# Sheet5.net
KiCad netlist of a schematic drawn in Altium Designer
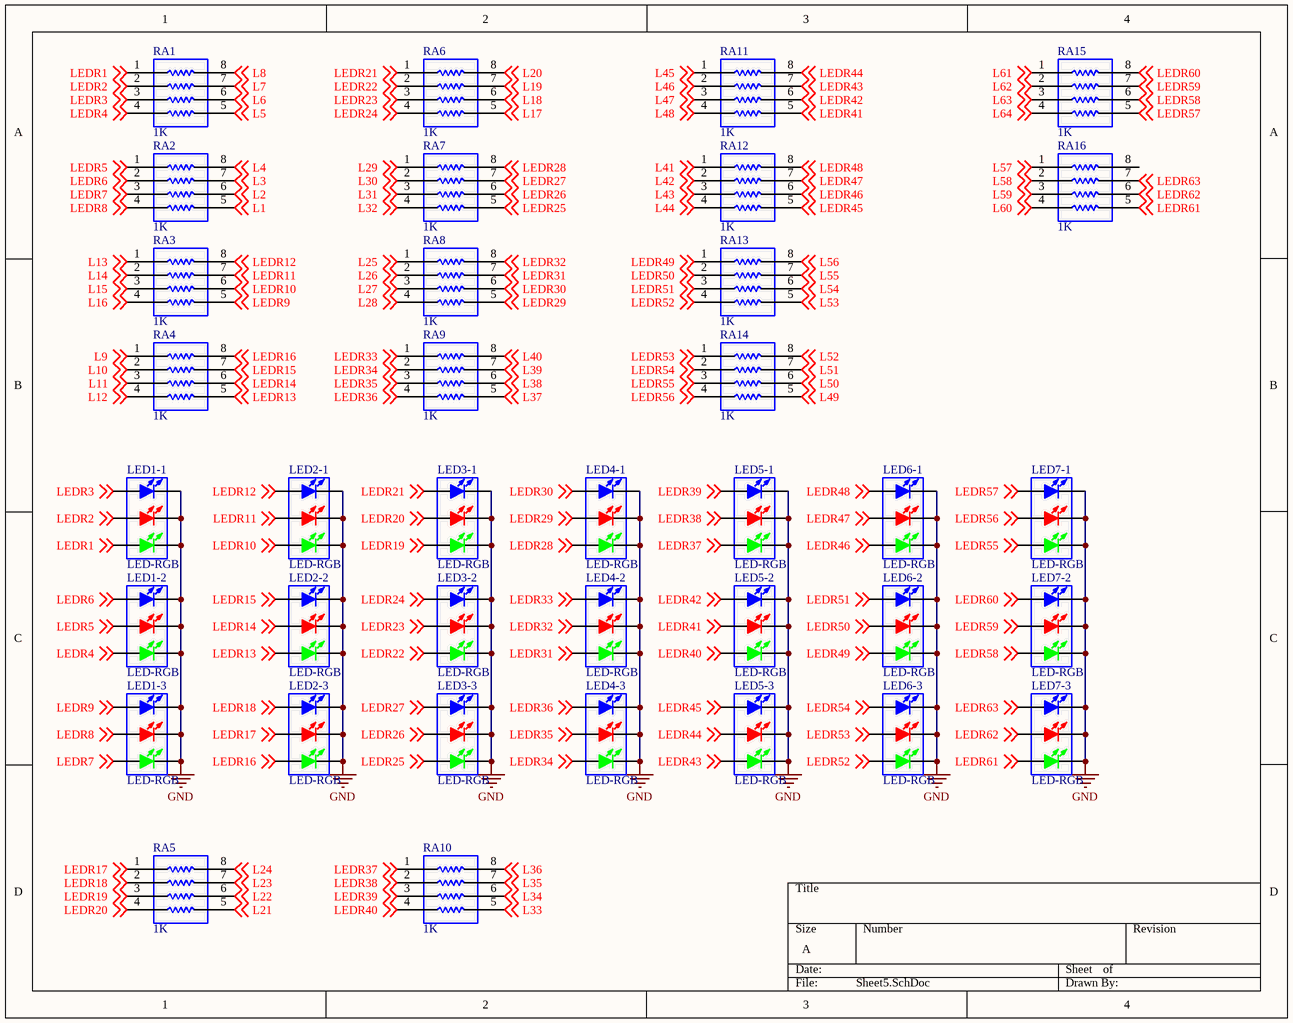
[diagram p0: Sheet5.SchDoc]

(export (version "E")
  (design (tool "Eeschema 10.0.6"))
  (components
    (comp (ref "LED1-1")
      (value "LED-RGB")
      (footprint "LED 5050")
      (description "Three primary color LED")
      (fields (field (name "版权归属") "源创客"))
      (libsource (lib "LED") (part "LED-RGB"))
    )
    (comp (ref "LED1-2")
      (value "LED-RGB")
      (footprint "LED 5050")
      (description "Three primary color LED")
      (fields (field (name "版权归属") "源创客"))
      (libsource (lib "LED") (part "LED-RGB"))
    )
    (comp (ref "LED1-3")
      (value "LED-RGB")
      (footprint "LED 5050")
      (description "Three primary color LED")
      (fields (field (name "版权归属") "源创客"))
      (libsource (lib "LED") (part "LED-RGB"))
    )
    (comp (ref "LED2-1")
      (value "LED-RGB")
      (footprint "LED 5050")
      (description "Three primary color LED")
      (fields (field (name "版权归属") "源创客"))
      (libsource (lib "LED") (part "LED-RGB"))
    )
    (comp (ref "LED2-2")
      (value "LED-RGB")
      (footprint "LED 5050")
      (description "Three primary color LED")
      (fields (field (name "版权归属") "源创客"))
      (libsource (lib "LED") (part "LED-RGB"))
    )
    (comp (ref "LED2-3")
      (value "LED-RGB")
      (footprint "LED 5050")
      (description "Three primary color LED")
      (fields (field (name "版权归属") "源创客"))
      (libsource (lib "LED") (part "LED-RGB"))
    )
    (comp (ref "LED3-1")
      (value "LED-RGB")
      (footprint "LED 5050")
      (description "Three primary color LED")
      (fields (field (name "版权归属") "源创客"))
      (libsource (lib "LED") (part "LED-RGB"))
    )
    (comp (ref "LED3-2")
      (value "LED-RGB")
      (footprint "LED 5050")
      (description "Three primary color LED")
      (fields (field (name "版权归属") "源创客"))
      (libsource (lib "LED") (part "LED-RGB"))
    )
    (comp (ref "LED3-3")
      (value "LED-RGB")
      (footprint "LED 5050")
      (description "Three primary color LED")
      (fields (field (name "版权归属") "源创客"))
      (libsource (lib "LED") (part "LED-RGB"))
    )
    (comp (ref "LED4-1")
      (value "LED-RGB")
      (footprint "LED 5050")
      (description "Three primary color LED")
      (fields (field (name "版权归属") "源创客"))
      (libsource (lib "LED") (part "LED-RGB"))
    )
    (comp (ref "LED4-2")
      (value "LED-RGB")
      (footprint "LED 5050")
      (description "Three primary color LED")
      (fields (field (name "版权归属") "源创客"))
      (libsource (lib "LED") (part "LED-RGB"))
    )
    (comp (ref "LED4-3")
      (value "LED-RGB")
      (footprint "LED 5050")
      (description "Three primary color LED")
      (fields (field (name "版权归属") "源创客"))
      (libsource (lib "LED") (part "LED-RGB"))
    )
    (comp (ref "LED5-1")
      (value "LED-RGB")
      (footprint "LED 5050")
      (description "Three primary color LED")
      (fields (field (name "版权归属") "源创客"))
      (libsource (lib "LED") (part "LED-RGB"))
    )
    (comp (ref "LED5-2")
      (value "LED-RGB")
      (footprint "LED 5050")
      (description "Three primary color LED")
      (fields (field (name "版权归属") "源创客"))
      (libsource (lib "LED") (part "LED-RGB"))
    )
    (comp (ref "LED5-3")
      (value "LED-RGB")
      (footprint "LED 5050")
      (description "Three primary color LED")
      (fields (field (name "版权归属") "源创客"))
      (libsource (lib "LED") (part "LED-RGB"))
    )
    (comp (ref "LED6-1")
      (value "LED-RGB")
      (footprint "LED 5050")
      (description "Three primary color LED")
      (fields (field (name "版权归属") "源创客"))
      (libsource (lib "LED") (part "LED-RGB"))
    )
    (comp (ref "LED6-2")
      (value "LED-RGB")
      (footprint "LED 5050")
      (description "Three primary color LED")
      (fields (field (name "版权归属") "源创客"))
      (libsource (lib "LED") (part "LED-RGB"))
    )
    (comp (ref "LED6-3")
      (value "LED-RGB")
      (footprint "LED 5050")
      (description "Three primary color LED")
      (fields (field (name "版权归属") "源创客"))
      (libsource (lib "LED") (part "LED-RGB"))
    )
    (comp (ref "LED7-1")
      (value "LED-RGB")
      (footprint "LED 5050")
      (description "Three primary color LED")
      (fields (field (name "版权归属") "源创客"))
      (libsource (lib "LED") (part "LED-RGB"))
    )
    (comp (ref "LED7-2")
      (value "LED-RGB")
      (footprint "LED 5050")
      (description "Three primary color LED")
      (fields (field (name "版权归属") "源创客"))
      (libsource (lib "LED") (part "LED-RGB"))
    )
    (comp (ref "LED7-3")
      (value "LED-RGB")
      (footprint "LED 5050")
      (description "Three primary color LED")
      (fields (field (name "版权归属") "源创客"))
      (libsource (lib "LED") (part "LED-RGB"))
    )
    (comp (ref "RA1")
      (value "1K")
      (footprint "RA1206 (4x0603)")
      (description "4 way Chip Resistor Array")
      (libsource (lib "Passive (Resistor-Capacitor-Inductor-Veristor-Ferrite)") (part "R-ARR"))
    )
    (comp (ref "RA2")
      (value "1K")
      (footprint "RA1206 (4x0603)")
      (description "4 way Chip Resistor Array")
      (libsource (lib "Passive (Resistor-Capacitor-Inductor-Veristor-Ferrite)") (part "R-ARR"))
    )
    (comp (ref "RA3")
      (value "1K")
      (footprint "RA1206 (4x0603)")
      (description "4 way Chip Resistor Array")
      (libsource (lib "Passive (Resistor-Capacitor-Inductor-Veristor-Ferrite)") (part "R-ARR"))
    )
    (comp (ref "RA4")
      (value "1K")
      (footprint "RA1206 (4x0603)")
      (description "4 way Chip Resistor Array")
      (libsource (lib "Passive (Resistor-Capacitor-Inductor-Veristor-Ferrite)") (part "R-ARR"))
    )
    (comp (ref "RA5")
      (value "1K")
      (footprint "RA1206 (4x0603)")
      (description "4 way Chip Resistor Array")
      (libsource (lib "Passive (Resistor-Capacitor-Inductor-Veristor-Ferrite)") (part "R-ARR"))
    )
    (comp (ref "RA6")
      (value "1K")
      (footprint "RA1206 (4x0603)")
      (description "4 way Chip Resistor Array")
      (libsource (lib "Passive (Resistor-Capacitor-Inductor-Veristor-Ferrite)") (part "R-ARR"))
    )
    (comp (ref "RA7")
      (value "1K")
      (footprint "RA1206 (4x0603)")
      (description "4 way Chip Resistor Array")
      (libsource (lib "Passive (Resistor-Capacitor-Inductor-Veristor-Ferrite)") (part "R-ARR"))
    )
    (comp (ref "RA8")
      (value "1K")
      (footprint "RA1206 (4x0603)")
      (description "4 way Chip Resistor Array")
      (libsource (lib "Passive (Resistor-Capacitor-Inductor-Veristor-Ferrite)") (part "R-ARR"))
    )
    (comp (ref "RA9")
      (value "1K")
      (footprint "RA1206 (4x0603)")
      (description "4 way Chip Resistor Array")
      (libsource (lib "Passive (Resistor-Capacitor-Inductor-Veristor-Ferrite)") (part "R-ARR"))
    )
    (comp (ref "RA10")
      (value "1K")
      (footprint "RA1206 (4x0603)")
      (description "4 way Chip Resistor Array")
      (libsource (lib "Passive (Resistor-Capacitor-Inductor-Veristor-Ferrite)") (part "R-ARR"))
    )
    (comp (ref "RA11")
      (value "1K")
      (footprint "RA1206 (4x0603)")
      (description "4 way Chip Resistor Array")
      (libsource (lib "Passive (Resistor-Capacitor-Inductor-Veristor-Ferrite)") (part "R-ARR"))
    )
    (comp (ref "RA12")
      (value "1K")
      (footprint "RA1206 (4x0603)")
      (description "4 way Chip Resistor Array")
      (libsource (lib "Passive (Resistor-Capacitor-Inductor-Veristor-Ferrite)") (part "R-ARR"))
    )
    (comp (ref "RA13")
      (value "1K")
      (footprint "RA1206 (4x0603)")
      (description "4 way Chip Resistor Array")
      (libsource (lib "Passive (Resistor-Capacitor-Inductor-Veristor-Ferrite)") (part "R-ARR"))
    )
    (comp (ref "RA14")
      (value "1K")
      (footprint "RA1206 (4x0603)")
      (description "4 way Chip Resistor Array")
      (libsource (lib "Passive (Resistor-Capacitor-Inductor-Veristor-Ferrite)") (part "R-ARR"))
    )
    (comp (ref "RA15")
      (value "1K")
      (footprint "RA1206 (4x0603)")
      (description "4 way Chip Resistor Array")
      (libsource (lib "Passive (Resistor-Capacitor-Inductor-Veristor-Ferrite)") (part "R-ARR"))
    )
    (comp (ref "RA16")
      (value "1K")
      (footprint "RA1206 (4x0603)")
      (description "4 way Chip Resistor Array")
      (libsource (lib "Passive (Resistor-Capacitor-Inductor-Veristor-Ferrite)") (part "R-ARR"))
    )
  )
  (nets
    (net (code "1") (name "GND") (class "Default")
      (node (ref "LED1-1") (pin "2") (pinfunction "BULE_K_2") (pintype "passive"))
      (node (ref "LED1-1") (pin "4") (pinfunction "RED_K_4") (pintype "passive"))
      (node (ref "LED1-1") (pin "6") (pinfunction "GREEN_K_6") (pintype "passive"))
      (node (ref "LED1-2") (pin "2") (pinfunction "BULE_K_2") (pintype "passive"))
      (node (ref "LED1-2") (pin "4") (pinfunction "RED_K_4") (pintype "passive"))
      (node (ref "LED1-2") (pin "6") (pinfunction "GREEN_K_6") (pintype "passive"))
      (node (ref "LED1-3") (pin "2") (pinfunction "BULE_K_2") (pintype "passive"))
      (node (ref "LED1-3") (pin "4") (pinfunction "RED_K_4") (pintype "passive"))
      (node (ref "LED1-3") (pin "6") (pinfunction "GREEN_K_6") (pintype "passive"))
      (node (ref "LED2-1") (pin "2") (pinfunction "BULE_K_2") (pintype "passive"))
      (node (ref "LED2-1") (pin "4") (pinfunction "RED_K_4") (pintype "passive"))
      (node (ref "LED2-1") (pin "6") (pinfunction "GREEN_K_6") (pintype "passive"))
      (node (ref "LED2-2") (pin "2") (pinfunction "BULE_K_2") (pintype "passive"))
      (node (ref "LED2-2") (pin "4") (pinfunction "RED_K_4") (pintype "passive"))
      (node (ref "LED2-2") (pin "6") (pinfunction "GREEN_K_6") (pintype "passive"))
      (node (ref "LED2-3") (pin "2") (pinfunction "BULE_K_2") (pintype "passive"))
      (node (ref "LED2-3") (pin "4") (pinfunction "RED_K_4") (pintype "passive"))
      (node (ref "LED2-3") (pin "6") (pinfunction "GREEN_K_6") (pintype "passive"))
      (node (ref "LED3-1") (pin "2") (pinfunction "BULE_K_2") (pintype "passive"))
      (node (ref "LED3-1") (pin "4") (pinfunction "RED_K_4") (pintype "passive"))
      (node (ref "LED3-1") (pin "6") (pinfunction "GREEN_K_6") (pintype "passive"))
      (node (ref "LED3-2") (pin "2") (pinfunction "BULE_K_2") (pintype "passive"))
      (node (ref "LED3-2") (pin "4") (pinfunction "RED_K_4") (pintype "passive"))
      (node (ref "LED3-2") (pin "6") (pinfunction "GREEN_K_6") (pintype "passive"))
      (node (ref "LED3-3") (pin "2") (pinfunction "BULE_K_2") (pintype "passive"))
      (node (ref "LED3-3") (pin "4") (pinfunction "RED_K_4") (pintype "passive"))
      (node (ref "LED3-3") (pin "6") (pinfunction "GREEN_K_6") (pintype "passive"))
      (node (ref "LED4-1") (pin "2") (pinfunction "BULE_K_2") (pintype "passive"))
      (node (ref "LED4-1") (pin "4") (pinfunction "RED_K_4") (pintype "passive"))
      (node (ref "LED4-1") (pin "6") (pinfunction "GREEN_K_6") (pintype "passive"))
      (node (ref "LED4-2") (pin "2") (pinfunction "BULE_K_2") (pintype "passive"))
      (node (ref "LED4-2") (pin "4") (pinfunction "RED_K_4") (pintype "passive"))
      (node (ref "LED4-2") (pin "6") (pinfunction "GREEN_K_6") (pintype "passive"))
      (node (ref "LED4-3") (pin "2") (pinfunction "BULE_K_2") (pintype "passive"))
      (node (ref "LED4-3") (pin "4") (pinfunction "RED_K_4") (pintype "passive"))
      (node (ref "LED4-3") (pin "6") (pinfunction "GREEN_K_6") (pintype "passive"))
      (node (ref "LED5-1") (pin "2") (pinfunction "BULE_K_2") (pintype "passive"))
      (node (ref "LED5-1") (pin "4") (pinfunction "RED_K_4") (pintype "passive"))
      (node (ref "LED5-1") (pin "6") (pinfunction "GREEN_K_6") (pintype "passive"))
      (node (ref "LED5-2") (pin "2") (pinfunction "BULE_K_2") (pintype "passive"))
      (node (ref "LED5-2") (pin "4") (pinfunction "RED_K_4") (pintype "passive"))
      (node (ref "LED5-2") (pin "6") (pinfunction "GREEN_K_6") (pintype "passive"))
      (node (ref "LED5-3") (pin "2") (pinfunction "BULE_K_2") (pintype "passive"))
      (node (ref "LED5-3") (pin "4") (pinfunction "RED_K_4") (pintype "passive"))
      (node (ref "LED5-3") (pin "6") (pinfunction "GREEN_K_6") (pintype "passive"))
      (node (ref "LED6-1") (pin "2") (pinfunction "BULE_K_2") (pintype "passive"))
      (node (ref "LED6-1") (pin "4") (pinfunction "RED_K_4") (pintype "passive"))
      (node (ref "LED6-1") (pin "6") (pinfunction "GREEN_K_6") (pintype "passive"))
      (node (ref "LED6-2") (pin "2") (pinfunction "BULE_K_2") (pintype "passive"))
      (node (ref "LED6-2") (pin "4") (pinfunction "RED_K_4") (pintype "passive"))
      (node (ref "LED6-2") (pin "6") (pinfunction "GREEN_K_6") (pintype "passive"))
      (node (ref "LED6-3") (pin "2") (pinfunction "BULE_K_2") (pintype "passive"))
      (node (ref "LED6-3") (pin "4") (pinfunction "RED_K_4") (pintype "passive"))
      (node (ref "LED6-3") (pin "6") (pinfunction "GREEN_K_6") (pintype "passive"))
      (node (ref "LED7-1") (pin "2") (pinfunction "BULE_K_2") (pintype "passive"))
      (node (ref "LED7-1") (pin "4") (pinfunction "RED_K_4") (pintype "passive"))
      (node (ref "LED7-1") (pin "6") (pinfunction "GREEN_K_6") (pintype "passive"))
      (node (ref "LED7-2") (pin "2") (pinfunction "BULE_K_2") (pintype "passive"))
      (node (ref "LED7-2") (pin "4") (pinfunction "RED_K_4") (pintype "passive"))
      (node (ref "LED7-2") (pin "6") (pinfunction "GREEN_K_6") (pintype "passive"))
      (node (ref "LED7-3") (pin "2") (pinfunction "BULE_K_2") (pintype "passive"))
      (node (ref "LED7-3") (pin "4") (pinfunction "RED_K_4") (pintype "passive"))
      (node (ref "LED7-3") (pin "6") (pinfunction "GREEN_K_6") (pintype "passive"))
    )
    (net (code "2") (name "L1") (class "Default")
      (node (ref "RA2") (pin "5") (pinfunction "5_5") (pintype "passive"))
    )
    (net (code "3") (name "L2") (class "Default")
      (node (ref "RA2") (pin "6") (pinfunction "6_6") (pintype "passive"))
    )
    (net (code "4") (name "L3") (class "Default")
      (node (ref "RA2") (pin "7") (pinfunction "7_7") (pintype "passive"))
    )
    (net (code "5") (name "L4") (class "Default")
      (node (ref "RA2") (pin "8") (pinfunction "8_8") (pintype "passive"))
    )
    (net (code "6") (name "L5") (class "Default")
      (node (ref "RA1") (pin "5") (pinfunction "5_5") (pintype "passive"))
    )
    (net (code "7") (name "L6") (class "Default")
      (node (ref "RA1") (pin "6") (pinfunction "6_6") (pintype "passive"))
    )
    (net (code "8") (name "L7") (class "Default")
      (node (ref "RA1") (pin "7") (pinfunction "7_7") (pintype "passive"))
    )
    (net (code "9") (name "L8") (class "Default")
      (node (ref "RA1") (pin "8") (pinfunction "8_8") (pintype "passive"))
    )
    (net (code "10") (name "L9") (class "Default")
      (node (ref "RA4") (pin "1") (pinfunction "1_1") (pintype "passive"))
    )
    (net (code "11") (name "L10") (class "Default")
      (node (ref "RA4") (pin "2") (pinfunction "2_2") (pintype "passive"))
    )
    (net (code "12") (name "L11") (class "Default")
      (node (ref "RA4") (pin "3") (pinfunction "3_3") (pintype "passive"))
    )
    (net (code "13") (name "L12") (class "Default")
      (node (ref "RA4") (pin "4") (pinfunction "4_4") (pintype "passive"))
    )
    (net (code "14") (name "L13") (class "Default")
      (node (ref "RA3") (pin "1") (pinfunction "1_1") (pintype "passive"))
    )
    (net (code "15") (name "L14") (class "Default")
      (node (ref "RA3") (pin "2") (pinfunction "2_2") (pintype "passive"))
    )
    (net (code "16") (name "L15") (class "Default")
      (node (ref "RA3") (pin "3") (pinfunction "3_3") (pintype "passive"))
    )
    (net (code "17") (name "L16") (class "Default")
      (node (ref "RA3") (pin "4") (pinfunction "4_4") (pintype "passive"))
    )
    (net (code "18") (name "L17") (class "Default")
      (node (ref "RA6") (pin "5") (pinfunction "5_5") (pintype "passive"))
    )
    (net (code "19") (name "L18") (class "Default")
      (node (ref "RA6") (pin "6") (pinfunction "6_6") (pintype "passive"))
    )
    (net (code "20") (name "L19") (class "Default")
      (node (ref "RA6") (pin "7") (pinfunction "7_7") (pintype "passive"))
    )
    (net (code "21") (name "L20") (class "Default")
      (node (ref "RA6") (pin "8") (pinfunction "8_8") (pintype "passive"))
    )
    (net (code "22") (name "L21") (class "Default")
      (node (ref "RA5") (pin "5") (pinfunction "5_5") (pintype "passive"))
    )
    (net (code "23") (name "L22") (class "Default")
      (node (ref "RA5") (pin "6") (pinfunction "6_6") (pintype "passive"))
    )
    (net (code "24") (name "L23") (class "Default")
      (node (ref "RA5") (pin "7") (pinfunction "7_7") (pintype "passive"))
    )
    (net (code "25") (name "L24") (class "Default")
      (node (ref "RA5") (pin "8") (pinfunction "8_8") (pintype "passive"))
    )
    (net (code "26") (name "L25") (class "Default")
      (node (ref "RA8") (pin "1") (pinfunction "1_1") (pintype "passive"))
    )
    (net (code "27") (name "L26") (class "Default")
      (node (ref "RA8") (pin "2") (pinfunction "2_2") (pintype "passive"))
    )
    (net (code "28") (name "L27") (class "Default")
      (node (ref "RA8") (pin "3") (pinfunction "3_3") (pintype "passive"))
    )
    (net (code "29") (name "L28") (class "Default")
      (node (ref "RA8") (pin "4") (pinfunction "4_4") (pintype "passive"))
    )
    (net (code "30") (name "L29") (class "Default")
      (node (ref "RA7") (pin "1") (pinfunction "1_1") (pintype "passive"))
    )
    (net (code "31") (name "L30") (class "Default")
      (node (ref "RA7") (pin "2") (pinfunction "2_2") (pintype "passive"))
    )
    (net (code "32") (name "L31") (class "Default")
      (node (ref "RA7") (pin "3") (pinfunction "3_3") (pintype "passive"))
    )
    (net (code "33") (name "L32") (class "Default")
      (node (ref "RA7") (pin "4") (pinfunction "4_4") (pintype "passive"))
    )
    (net (code "34") (name "L33") (class "Default")
      (node (ref "RA10") (pin "5") (pinfunction "5_5") (pintype "passive"))
    )
    (net (code "35") (name "L34") (class "Default")
      (node (ref "RA10") (pin "6") (pinfunction "6_6") (pintype "passive"))
    )
    (net (code "36") (name "L35") (class "Default")
      (node (ref "RA10") (pin "7") (pinfunction "7_7") (pintype "passive"))
    )
    (net (code "37") (name "L36") (class "Default")
      (node (ref "RA10") (pin "8") (pinfunction "8_8") (pintype "passive"))
    )
    (net (code "38") (name "L37") (class "Default")
      (node (ref "RA9") (pin "5") (pinfunction "5_5") (pintype "passive"))
    )
    (net (code "39") (name "L38") (class "Default")
      (node (ref "RA9") (pin "6") (pinfunction "6_6") (pintype "passive"))
    )
    (net (code "40") (name "L39") (class "Default")
      (node (ref "RA9") (pin "7") (pinfunction "7_7") (pintype "passive"))
    )
    (net (code "41") (name "L40") (class "Default")
      (node (ref "RA9") (pin "8") (pinfunction "8_8") (pintype "passive"))
    )
    (net (code "42") (name "L41") (class "Default")
      (node (ref "RA12") (pin "1") (pinfunction "1_1") (pintype "passive"))
    )
    (net (code "43") (name "L42") (class "Default")
      (node (ref "RA12") (pin "2") (pinfunction "2_2") (pintype "passive"))
    )
    (net (code "44") (name "L43") (class "Default")
      (node (ref "RA12") (pin "3") (pinfunction "3_3") (pintype "passive"))
    )
    (net (code "45") (name "L44") (class "Default")
      (node (ref "RA12") (pin "4") (pinfunction "4_4") (pintype "passive"))
    )
    (net (code "46") (name "L45") (class "Default")
      (node (ref "RA11") (pin "1") (pinfunction "1_1") (pintype "passive"))
    )
    (net (code "47") (name "L46") (class "Default")
      (node (ref "RA11") (pin "2") (pinfunction "2_2") (pintype "passive"))
    )
    (net (code "48") (name "L47") (class "Default")
      (node (ref "RA11") (pin "3") (pinfunction "3_3") (pintype "passive"))
    )
    (net (code "49") (name "L48") (class "Default")
      (node (ref "RA11") (pin "4") (pinfunction "4_4") (pintype "passive"))
    )
    (net (code "50") (name "L49") (class "Default")
      (node (ref "RA14") (pin "5") (pinfunction "5_5") (pintype "passive"))
    )
    (net (code "51") (name "L50") (class "Default")
      (node (ref "RA14") (pin "6") (pinfunction "6_6") (pintype "passive"))
    )
    (net (code "52") (name "L51") (class "Default")
      (node (ref "RA14") (pin "7") (pinfunction "7_7") (pintype "passive"))
    )
    (net (code "53") (name "L52") (class "Default")
      (node (ref "RA14") (pin "8") (pinfunction "8_8") (pintype "passive"))
    )
    (net (code "54") (name "L53") (class "Default")
      (node (ref "RA13") (pin "5") (pinfunction "5_5") (pintype "passive"))
    )
    (net (code "55") (name "L54") (class "Default")
      (node (ref "RA13") (pin "6") (pinfunction "6_6") (pintype "passive"))
    )
    (net (code "56") (name "L55") (class "Default")
      (node (ref "RA13") (pin "7") (pinfunction "7_7") (pintype "passive"))
    )
    (net (code "57") (name "L56") (class "Default")
      (node (ref "RA13") (pin "8") (pinfunction "8_8") (pintype "passive"))
    )
    (net (code "58") (name "L57") (class "Default")
      (node (ref "RA16") (pin "1") (pinfunction "1_1") (pintype "passive"))
    )
    (net (code "59") (name "L58") (class "Default")
      (node (ref "RA16") (pin "2") (pinfunction "2_2") (pintype "passive"))
    )
    (net (code "60") (name "L59") (class "Default")
      (node (ref "RA16") (pin "3") (pinfunction "3_3") (pintype "passive"))
    )
    (net (code "61") (name "L60") (class "Default")
      (node (ref "RA16") (pin "4") (pinfunction "4_4") (pintype "passive"))
    )
    (net (code "62") (name "L61") (class "Default")
      (node (ref "RA15") (pin "1") (pinfunction "1_1") (pintype "passive"))
    )
    (net (code "63") (name "L62") (class "Default")
      (node (ref "RA15") (pin "2") (pinfunction "2_2") (pintype "passive"))
    )
    (net (code "64") (name "L63") (class "Default")
      (node (ref "RA15") (pin "3") (pinfunction "3_3") (pintype "passive"))
    )
    (net (code "65") (name "L64") (class "Default")
      (node (ref "RA15") (pin "4") (pinfunction "4_4") (pintype "passive"))
    )
    (net (code "66") (name "LEDR1") (class "Default")
      (node (ref "LED1-1") (pin "5") (pinfunction "GREEN_A_5") (pintype "passive"))
      (node (ref "RA1") (pin "1") (pinfunction "1_1") (pintype "passive"))
    )
    (net (code "67") (name "LEDR2") (class "Default")
      (node (ref "LED1-1") (pin "3") (pinfunction "RED_A_3") (pintype "passive"))
      (node (ref "RA1") (pin "2") (pinfunction "2_2") (pintype "passive"))
    )
    (net (code "68") (name "LEDR3") (class "Default")
      (node (ref "LED1-1") (pin "1") (pinfunction "BULE_A_1") (pintype "passive"))
      (node (ref "RA1") (pin "3") (pinfunction "3_3") (pintype "passive"))
    )
    (net (code "69") (name "LEDR4") (class "Default")
      (node (ref "LED1-2") (pin "5") (pinfunction "GREEN_A_5") (pintype "passive"))
      (node (ref "RA1") (pin "4") (pinfunction "4_4") (pintype "passive"))
    )
    (net (code "70") (name "LEDR5") (class "Default")
      (node (ref "LED1-2") (pin "3") (pinfunction "RED_A_3") (pintype "passive"))
      (node (ref "RA2") (pin "1") (pinfunction "1_1") (pintype "passive"))
    )
    (net (code "71") (name "LEDR6") (class "Default")
      (node (ref "LED1-2") (pin "1") (pinfunction "BULE_A_1") (pintype "passive"))
      (node (ref "RA2") (pin "2") (pinfunction "2_2") (pintype "passive"))
    )
    (net (code "72") (name "LEDR7") (class "Default")
      (node (ref "LED1-3") (pin "5") (pinfunction "GREEN_A_5") (pintype "passive"))
      (node (ref "RA2") (pin "3") (pinfunction "3_3") (pintype "passive"))
    )
    (net (code "73") (name "LEDR8") (class "Default")
      (node (ref "LED1-3") (pin "3") (pinfunction "RED_A_3") (pintype "passive"))
      (node (ref "RA2") (pin "4") (pinfunction "4_4") (pintype "passive"))
    )
    (net (code "74") (name "LEDR9") (class "Default")
      (node (ref "LED1-3") (pin "1") (pinfunction "BULE_A_1") (pintype "passive"))
      (node (ref "RA3") (pin "5") (pinfunction "5_5") (pintype "passive"))
    )
    (net (code "75") (name "LEDR10") (class "Default")
      (node (ref "LED2-1") (pin "5") (pinfunction "GREEN_A_5") (pintype "passive"))
      (node (ref "RA3") (pin "6") (pinfunction "6_6") (pintype "passive"))
    )
    (net (code "76") (name "LEDR11") (class "Default")
      (node (ref "LED2-1") (pin "3") (pinfunction "RED_A_3") (pintype "passive"))
      (node (ref "RA3") (pin "7") (pinfunction "7_7") (pintype "passive"))
    )
    (net (code "77") (name "LEDR12") (class "Default")
      (node (ref "LED2-1") (pin "1") (pinfunction "BULE_A_1") (pintype "passive"))
      (node (ref "RA3") (pin "8") (pinfunction "8_8") (pintype "passive"))
    )
    (net (code "78") (name "LEDR13") (class "Default")
      (node (ref "LED2-2") (pin "5") (pinfunction "GREEN_A_5") (pintype "passive"))
      (node (ref "RA4") (pin "5") (pinfunction "5_5") (pintype "passive"))
    )
    (net (code "79") (name "LEDR14") (class "Default")
      (node (ref "LED2-2") (pin "3") (pinfunction "RED_A_3") (pintype "passive"))
      (node (ref "RA4") (pin "6") (pinfunction "6_6") (pintype "passive"))
    )
    (net (code "80") (name "LEDR15") (class "Default")
      (node (ref "LED2-2") (pin "1") (pinfunction "BULE_A_1") (pintype "passive"))
      (node (ref "RA4") (pin "7") (pinfunction "7_7") (pintype "passive"))
    )
    (net (code "81") (name "LEDR16") (class "Default")
      (node (ref "LED2-3") (pin "5") (pinfunction "GREEN_A_5") (pintype "passive"))
      (node (ref "RA4") (pin "8") (pinfunction "8_8") (pintype "passive"))
    )
    (net (code "82") (name "LEDR17") (class "Default")
      (node (ref "LED2-3") (pin "3") (pinfunction "RED_A_3") (pintype "passive"))
      (node (ref "RA5") (pin "1") (pinfunction "1_1") (pintype "passive"))
    )
    (net (code "83") (name "LEDR18") (class "Default")
      (node (ref "LED2-3") (pin "1") (pinfunction "BULE_A_1") (pintype "passive"))
      (node (ref "RA5") (pin "2") (pinfunction "2_2") (pintype "passive"))
    )
    (net (code "84") (name "LEDR19") (class "Default")
      (node (ref "LED3-1") (pin "5") (pinfunction "GREEN_A_5") (pintype "passive"))
      (node (ref "RA5") (pin "3") (pinfunction "3_3") (pintype "passive"))
    )
    (net (code "85") (name "LEDR20") (class "Default")
      (node (ref "LED3-1") (pin "3") (pinfunction "RED_A_3") (pintype "passive"))
      (node (ref "RA5") (pin "4") (pinfunction "4_4") (pintype "passive"))
    )
    (net (code "86") (name "LEDR21") (class "Default")
      (node (ref "LED3-1") (pin "1") (pinfunction "BULE_A_1") (pintype "passive"))
      (node (ref "RA6") (pin "1") (pinfunction "1_1") (pintype "passive"))
    )
    (net (code "87") (name "LEDR22") (class "Default")
      (node (ref "LED3-2") (pin "5") (pinfunction "GREEN_A_5") (pintype "passive"))
      (node (ref "RA6") (pin "2") (pinfunction "2_2") (pintype "passive"))
    )
    (net (code "88") (name "LEDR23") (class "Default")
      (node (ref "LED3-2") (pin "3") (pinfunction "RED_A_3") (pintype "passive"))
      (node (ref "RA6") (pin "3") (pinfunction "3_3") (pintype "passive"))
    )
    (net (code "89") (name "LEDR24") (class "Default")
      (node (ref "LED3-2") (pin "1") (pinfunction "BULE_A_1") (pintype "passive"))
      (node (ref "RA6") (pin "4") (pinfunction "4_4") (pintype "passive"))
    )
    (net (code "90") (name "LEDR25") (class "Default")
      (node (ref "LED3-3") (pin "5") (pinfunction "GREEN_A_5") (pintype "passive"))
      (node (ref "RA7") (pin "5") (pinfunction "5_5") (pintype "passive"))
    )
    (net (code "91") (name "LEDR26") (class "Default")
      (node (ref "LED3-3") (pin "3") (pinfunction "RED_A_3") (pintype "passive"))
      (node (ref "RA7") (pin "6") (pinfunction "6_6") (pintype "passive"))
    )
    (net (code "92") (name "LEDR27") (class "Default")
      (node (ref "LED3-3") (pin "1") (pinfunction "BULE_A_1") (pintype "passive"))
      (node (ref "RA7") (pin "7") (pinfunction "7_7") (pintype "passive"))
    )
    (net (code "93") (name "LEDR28") (class "Default")
      (node (ref "LED4-1") (pin "5") (pinfunction "GREEN_A_5") (pintype "passive"))
      (node (ref "RA7") (pin "8") (pinfunction "8_8") (pintype "passive"))
    )
    (net (code "94") (name "LEDR29") (class "Default")
      (node (ref "LED4-1") (pin "3") (pinfunction "RED_A_3") (pintype "passive"))
      (node (ref "RA8") (pin "5") (pinfunction "5_5") (pintype "passive"))
    )
    (net (code "95") (name "LEDR30") (class "Default")
      (node (ref "LED4-1") (pin "1") (pinfunction "BULE_A_1") (pintype "passive"))
      (node (ref "RA8") (pin "6") (pinfunction "6_6") (pintype "passive"))
    )
    (net (code "96") (name "LEDR31") (class "Default")
      (node (ref "LED4-2") (pin "5") (pinfunction "GREEN_A_5") (pintype "passive"))
      (node (ref "RA8") (pin "7") (pinfunction "7_7") (pintype "passive"))
    )
    (net (code "97") (name "LEDR32") (class "Default")
      (node (ref "LED4-2") (pin "3") (pinfunction "RED_A_3") (pintype "passive"))
      (node (ref "RA8") (pin "8") (pinfunction "8_8") (pintype "passive"))
    )
    (net (code "98") (name "LEDR33") (class "Default")
      (node (ref "LED4-2") (pin "1") (pinfunction "BULE_A_1") (pintype "passive"))
      (node (ref "RA9") (pin "1") (pinfunction "1_1") (pintype "passive"))
    )
    (net (code "99") (name "LEDR34") (class "Default")
      (node (ref "LED4-3") (pin "5") (pinfunction "GREEN_A_5") (pintype "passive"))
      (node (ref "RA9") (pin "2") (pinfunction "2_2") (pintype "passive"))
    )
    (net (code "100") (name "LEDR35") (class "Default")
      (node (ref "LED4-3") (pin "3") (pinfunction "RED_A_3") (pintype "passive"))
      (node (ref "RA9") (pin "3") (pinfunction "3_3") (pintype "passive"))
    )
    (net (code "101") (name "LEDR36") (class "Default")
      (node (ref "LED4-3") (pin "1") (pinfunction "BULE_A_1") (pintype "passive"))
      (node (ref "RA9") (pin "4") (pinfunction "4_4") (pintype "passive"))
    )
    (net (code "102") (name "LEDR37") (class "Default")
      (node (ref "LED5-1") (pin "5") (pinfunction "GREEN_A_5") (pintype "passive"))
      (node (ref "RA10") (pin "1") (pinfunction "1_1") (pintype "passive"))
    )
    (net (code "103") (name "LEDR38") (class "Default")
      (node (ref "LED5-1") (pin "3") (pinfunction "RED_A_3") (pintype "passive"))
      (node (ref "RA10") (pin "2") (pinfunction "2_2") (pintype "passive"))
    )
    (net (code "104") (name "LEDR39") (class "Default")
      (node (ref "LED5-1") (pin "1") (pinfunction "BULE_A_1") (pintype "passive"))
      (node (ref "RA10") (pin "3") (pinfunction "3_3") (pintype "passive"))
    )
    (net (code "105") (name "LEDR40") (class "Default")
      (node (ref "LED5-2") (pin "5") (pinfunction "GREEN_A_5") (pintype "passive"))
      (node (ref "RA10") (pin "4") (pinfunction "4_4") (pintype "passive"))
    )
    (net (code "106") (name "LEDR41") (class "Default")
      (node (ref "LED5-2") (pin "3") (pinfunction "RED_A_3") (pintype "passive"))
      (node (ref "RA11") (pin "5") (pinfunction "5_5") (pintype "passive"))
    )
    (net (code "107") (name "LEDR42") (class "Default")
      (node (ref "LED5-2") (pin "1") (pinfunction "BULE_A_1") (pintype "passive"))
      (node (ref "RA11") (pin "6") (pinfunction "6_6") (pintype "passive"))
    )
    (net (code "108") (name "LEDR43") (class "Default")
      (node (ref "LED5-3") (pin "5") (pinfunction "GREEN_A_5") (pintype "passive"))
      (node (ref "RA11") (pin "7") (pinfunction "7_7") (pintype "passive"))
    )
    (net (code "109") (name "LEDR44") (class "Default")
      (node (ref "LED5-3") (pin "3") (pinfunction "RED_A_3") (pintype "passive"))
      (node (ref "RA11") (pin "8") (pinfunction "8_8") (pintype "passive"))
    )
    (net (code "110") (name "LEDR45") (class "Default")
      (node (ref "LED5-3") (pin "1") (pinfunction "BULE_A_1") (pintype "passive"))
      (node (ref "RA12") (pin "5") (pinfunction "5_5") (pintype "passive"))
    )
    (net (code "111") (name "LEDR46") (class "Default")
      (node (ref "LED6-1") (pin "5") (pinfunction "GREEN_A_5") (pintype "passive"))
      (node (ref "RA12") (pin "6") (pinfunction "6_6") (pintype "passive"))
    )
    (net (code "112") (name "LEDR47") (class "Default")
      (node (ref "LED6-1") (pin "3") (pinfunction "RED_A_3") (pintype "passive"))
      (node (ref "RA12") (pin "7") (pinfunction "7_7") (pintype "passive"))
    )
    (net (code "113") (name "LEDR48") (class "Default")
      (node (ref "LED6-1") (pin "1") (pinfunction "BULE_A_1") (pintype "passive"))
      (node (ref "RA12") (pin "8") (pinfunction "8_8") (pintype "passive"))
    )
    (net (code "114") (name "LEDR49") (class "Default")
      (node (ref "LED6-2") (pin "5") (pinfunction "GREEN_A_5") (pintype "passive"))
      (node (ref "RA13") (pin "1") (pinfunction "1_1") (pintype "passive"))
    )
    (net (code "115") (name "LEDR50") (class "Default")
      (node (ref "LED6-2") (pin "3") (pinfunction "RED_A_3") (pintype "passive"))
      (node (ref "RA13") (pin "2") (pinfunction "2_2") (pintype "passive"))
    )
    (net (code "116") (name "LEDR51") (class "Default")
      (node (ref "LED6-2") (pin "1") (pinfunction "BULE_A_1") (pintype "passive"))
      (node (ref "RA13") (pin "3") (pinfunction "3_3") (pintype "passive"))
    )
    (net (code "117") (name "LEDR52") (class "Default")
      (node (ref "LED6-3") (pin "5") (pinfunction "GREEN_A_5") (pintype "passive"))
      (node (ref "RA13") (pin "4") (pinfunction "4_4") (pintype "passive"))
    )
    (net (code "118") (name "LEDR53") (class "Default")
      (node (ref "LED6-3") (pin "3") (pinfunction "RED_A_3") (pintype "passive"))
      (node (ref "RA14") (pin "1") (pinfunction "1_1") (pintype "passive"))
    )
    (net (code "119") (name "LEDR54") (class "Default")
      (node (ref "LED6-3") (pin "1") (pinfunction "BULE_A_1") (pintype "passive"))
      (node (ref "RA14") (pin "2") (pinfunction "2_2") (pintype "passive"))
    )
    (net (code "120") (name "LEDR55") (class "Default")
      (node (ref "LED7-1") (pin "5") (pinfunction "GREEN_A_5") (pintype "passive"))
      (node (ref "RA14") (pin "3") (pinfunction "3_3") (pintype "passive"))
    )
    (net (code "121") (name "LEDR56") (class "Default")
      (node (ref "LED7-1") (pin "3") (pinfunction "RED_A_3") (pintype "passive"))
      (node (ref "RA14") (pin "4") (pinfunction "4_4") (pintype "passive"))
    )
    (net (code "122") (name "LEDR57") (class "Default")
      (node (ref "LED7-1") (pin "1") (pinfunction "BULE_A_1") (pintype "passive"))
      (node (ref "RA15") (pin "5") (pinfunction "5_5") (pintype "passive"))
    )
    (net (code "123") (name "LEDR58") (class "Default")
      (node (ref "LED7-2") (pin "5") (pinfunction "GREEN_A_5") (pintype "passive"))
      (node (ref "RA15") (pin "6") (pinfunction "6_6") (pintype "passive"))
    )
    (net (code "124") (name "LEDR59") (class "Default")
      (node (ref "LED7-2") (pin "3") (pinfunction "RED_A_3") (pintype "passive"))
      (node (ref "RA15") (pin "7") (pinfunction "7_7") (pintype "passive"))
    )
    (net (code "125") (name "LEDR60") (class "Default")
      (node (ref "LED7-2") (pin "1") (pinfunction "BULE_A_1") (pintype "passive"))
      (node (ref "RA15") (pin "8") (pinfunction "8_8") (pintype "passive"))
    )
    (net (code "126") (name "LEDR61") (class "Default")
      (node (ref "LED7-3") (pin "5") (pinfunction "GREEN_A_5") (pintype "passive"))
      (node (ref "RA16") (pin "5") (pinfunction "5_5") (pintype "passive"))
    )
    (net (code "127") (name "LEDR62") (class "Default")
      (node (ref "LED7-3") (pin "3") (pinfunction "RED_A_3") (pintype "passive"))
      (node (ref "RA16") (pin "6") (pinfunction "6_6") (pintype "passive"))
    )
    (net (code "128") (name "LEDR63") (class "Default")
      (node (ref "LED7-3") (pin "1") (pinfunction "BULE_A_1") (pintype "passive"))
      (node (ref "RA16") (pin "7") (pinfunction "7_7") (pintype "passive"))
    )
    (net (code "129") (name "unconnected-(RA16-Pad8)") (class "Default")
      (node (ref "RA16") (pin "8") (pinfunction "8_8") (pintype "passive"))
    )
  )
)
